# data_interface.net
KiCad netlist of a schematic drawn in Altium Designer
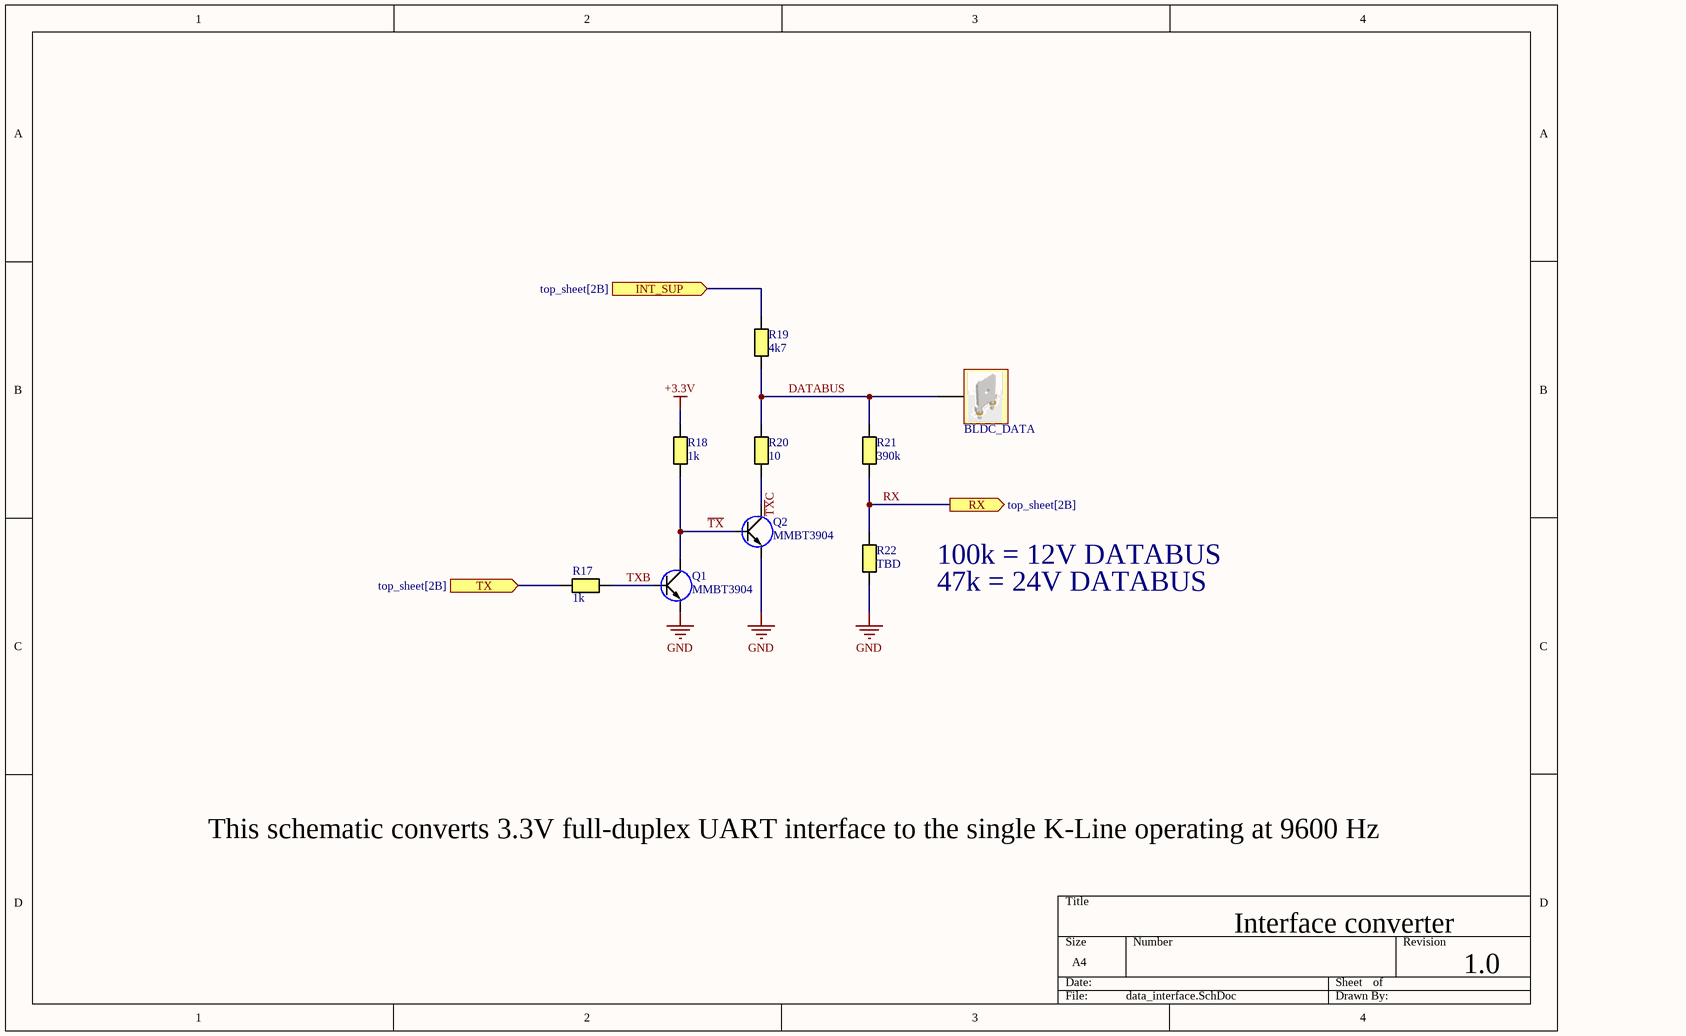
[diagram p0: data_interface.SchDoc]

(export (version "E")
  (design (tool "Eeschema 10.0.6"))
  (components
    (comp (ref "BLDC_DATA")
      (value "Crimp 6.3 single PCB")
      (footprint "Crimp 6.3mm single PCB")
      (description "Straight Mount Angle PCB Tab Terminal")
      (libsource (lib "Connectors") (part "Crimp 6.3 single PCB"))
    )
    (comp (ref "Q1")
      (value "MMBT3904")
      (footprint "SOT23")
      (description "NPN General Purpose Transistor")
      (libsource (lib "Transistors") (part "2N3904"))
    )
    (comp (ref "Q2")
      (value "MMBT3904")
      (footprint "SOT23")
      (description "NPN General Purpose Transistor")
      (libsource (lib "Transistors") (part "2N3904"))
    )
    (comp (ref "R17")
      (value "1k")
      (footprint "RESC0603(1608)_N")
      (description "Resistor Medium Density")
      (libsource (lib "Discrete") (part "Resistor M"))
    )
    (comp (ref "R18")
      (value "1k")
      (footprint "RESC0603(1608)_N")
      (description "Resistor Medium Density")
      (libsource (lib "") (part "Resistor M_1"))
    )
    (comp (ref "R19")
      (value "4k7")
      (footprint "RESC0603(1608)_N")
      (description "Resistor Medium Density")
      (libsource (lib "") (part "Resistor M_1"))
    )
    (comp (ref "R20")
      (value "10")
      (footprint "RESC0603(1608)_N")
      (description "Resistor Medium Density")
      (libsource (lib "") (part "Resistor M_1"))
    )
    (comp (ref "R21")
      (value "390k")
      (footprint "RESC0603(1608)_N")
      (description "Resistor Medium Density")
      (libsource (lib "") (part "Resistor M_1"))
    )
    (comp (ref "R22")
      (value "TBD")
      (footprint "RESC0603(1608)_N")
      (description "Resistor Medium Density")
      (libsource (lib "") (part "Resistor M_1"))
    )
  )
  (nets
    (net (code "1") (name "+3.3V") (class "Default")
      (node (ref "R18") (pin "2") (pinfunction "2_2") (pintype "passive"))
    )
    (net (code "2") (name "/DATABUS") (class "Default")
      (node (ref "BLDC_DATA") (pin "1") (pintype "passive"))
      (node (ref "R19") (pin "1") (pinfunction "1_1") (pintype "passive"))
      (node (ref "R20") (pin "2") (pinfunction "2_2") (pintype "passive"))
      (node (ref "R21") (pin "2") (pinfunction "2_2") (pintype "passive"))
    )
    (net (code "3") (name "/INT_SUP") (class "Default")
      (node (ref "R19") (pin "2") (pinfunction "2_2") (pintype "passive"))
    )
    (net (code "4") (name "/RX") (class "Default")
      (node (ref "R21") (pin "1") (pinfunction "1_1") (pintype "passive"))
      (node (ref "R22") (pin "2") (pinfunction "2_2") (pintype "passive"))
    )
    (net (code "5") (name "/TX") (class "Default")
      (node (ref "R17") (pin "1") (pinfunction "1_1") (pintype "passive"))
    )
    (net (code "6") (name "/TXB") (class "Default")
      (node (ref "Q1") (pin "1") (pinfunction "B_1") (pintype "passive"))
      (node (ref "R17") (pin "2") (pinfunction "2_2") (pintype "passive"))
    )
    (net (code "7") (name "/~{TX}") (class "Default")
      (node (ref "Q1") (pin "3") (pinfunction "C_3") (pintype "passive"))
      (node (ref "Q2") (pin "1") (pinfunction "B_1") (pintype "passive"))
      (node (ref "R18") (pin "1") (pinfunction "1_1") (pintype "passive"))
    )
    (net (code "8") (name "/~{TX}C") (class "Default")
      (node (ref "Q2") (pin "3") (pinfunction "C_3") (pintype "passive"))
      (node (ref "R20") (pin "1") (pinfunction "1_1") (pintype "passive"))
    )
    (net (code "9") (name "GND") (class "Default")
      (node (ref "Q1") (pin "2") (pinfunction "E_2") (pintype "passive"))
      (node (ref "Q2") (pin "2") (pinfunction "E_2") (pintype "passive"))
      (node (ref "R22") (pin "1") (pinfunction "1_1") (pintype "passive"))
    )
  )
)
